# Stort_kredslob.net
KiCad netlist of a schematic drawn in EAGLE
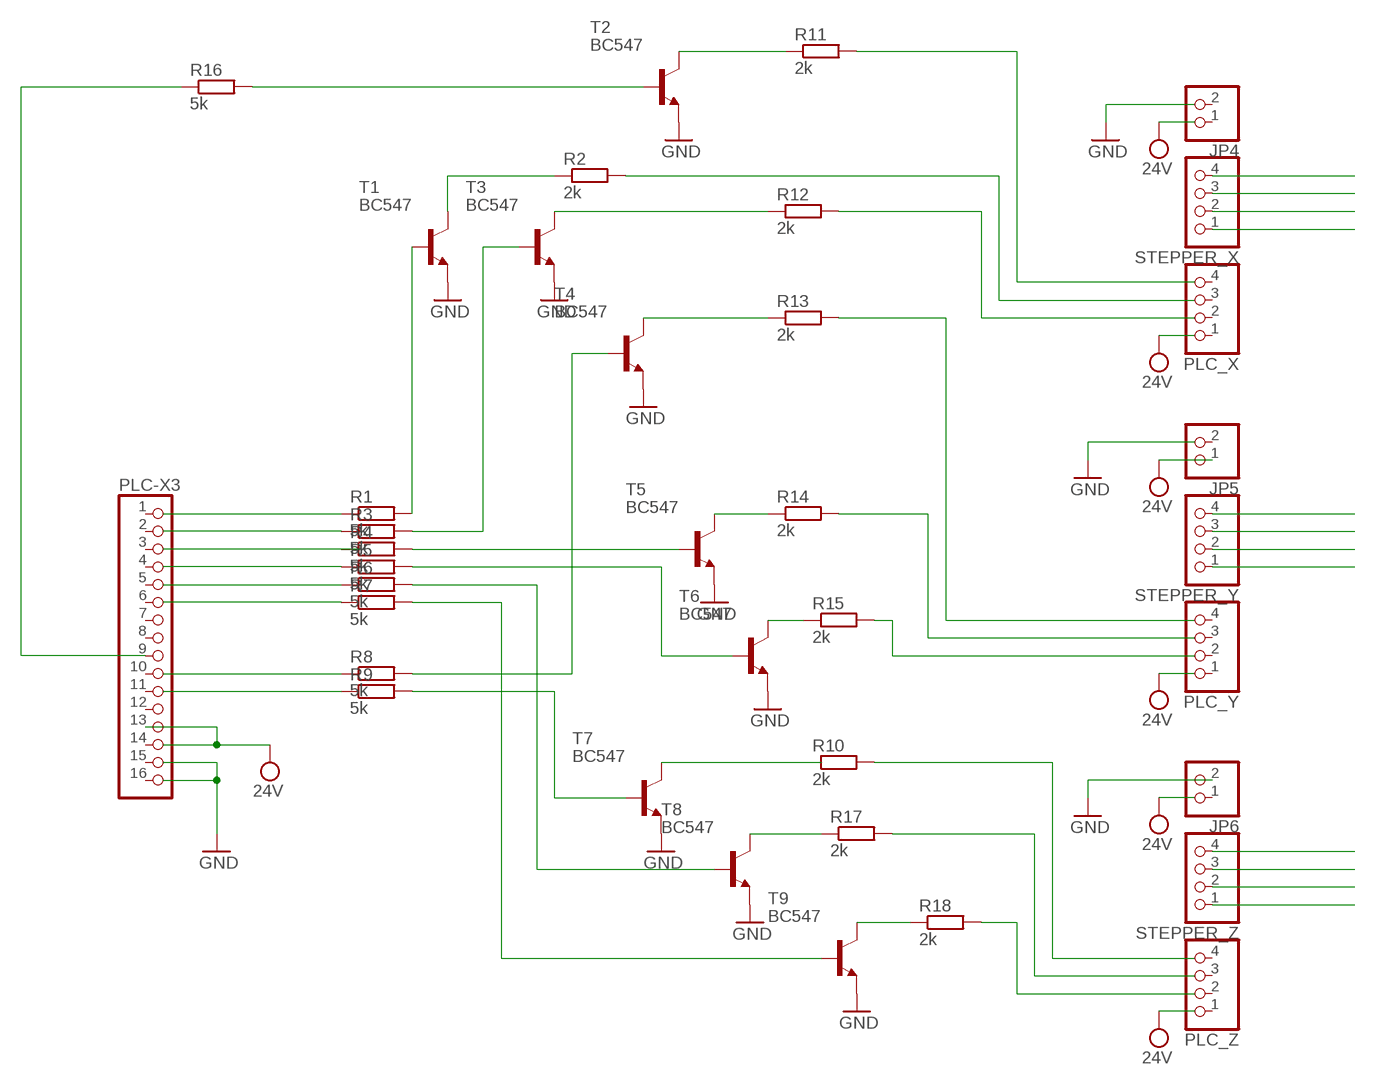
[diagram p0: schematic, sheet 1]

(export (version "E")
  (design (tool "Eeschema 10.0.6"))
  (components
    (comp (ref "JP4")
      (value "PINHD-1X2")
      (footprint "eagle-import:1X02")
      (libsource (lib "eagle-import") (part "PINHD-1X2"))
    )
    (comp (ref "JP5")
      (value "PINHD-1X2")
      (footprint "eagle-import:1X02")
      (libsource (lib "eagle-import") (part "PINHD-1X2"))
    )
    (comp (ref "JP6")
      (value "PINHD-1X2")
      (footprint "eagle-import:1X02")
      (libsource (lib "eagle-import") (part "PINHD-1X2"))
    )
    (comp (ref "PLC-X3")
      (value "PINHD-1X16")
      (footprint "eagle-import:1X16")
      (libsource (lib "eagle-import") (part "PINHD-1X16"))
    )
    (comp (ref "PLC_X")
      (value "PINHD-1X4")
      (footprint "eagle-import:1X04")
      (libsource (lib "eagle-import") (part "PINHD-1X4"))
    )
    (comp (ref "PLC_Y")
      (value "PINHD-1X4")
      (footprint "eagle-import:1X04")
      (libsource (lib "eagle-import") (part "PINHD-1X4"))
    )
    (comp (ref "PLC_Z")
      (value "PINHD-1X4")
      (footprint "eagle-import:1X04")
      (libsource (lib "eagle-import") (part "PINHD-1X4"))
    )
    (comp (ref "R1")
      (value "5k")
      (footprint "eagle-import:0207_10")
      (libsource (lib "eagle-import") (part "R-EU_0207/10"))
    )
    (comp (ref "R2")
      (value "2k")
      (footprint "eagle-import:0207_10")
      (libsource (lib "eagle-import") (part "R-EU_0207/10"))
    )
    (comp (ref "R3")
      (value "5k")
      (footprint "eagle-import:0207_10")
      (libsource (lib "eagle-import") (part "R-EU_0207/10"))
    )
    (comp (ref "R4")
      (value "5k")
      (footprint "eagle-import:0207_10")
      (libsource (lib "eagle-import") (part "R-EU_0207/10"))
    )
    (comp (ref "R5")
      (value "5k")
      (footprint "eagle-import:0207_10")
      (libsource (lib "eagle-import") (part "R-EU_0207/10"))
    )
    (comp (ref "R6")
      (value "5k")
      (footprint "eagle-import:0207_10")
      (libsource (lib "eagle-import") (part "R-EU_0207/10"))
    )
    (comp (ref "R7")
      (value "5k")
      (footprint "eagle-import:0207_10")
      (libsource (lib "eagle-import") (part "R-EU_0207/10"))
    )
    (comp (ref "R8")
      (value "5k")
      (footprint "eagle-import:0207_10")
      (libsource (lib "eagle-import") (part "R-EU_0207/10"))
    )
    (comp (ref "R9")
      (value "5k")
      (footprint "eagle-import:0207_10")
      (libsource (lib "eagle-import") (part "R-EU_0207/10"))
    )
    (comp (ref "R10")
      (value "2k")
      (footprint "eagle-import:0207_10")
      (libsource (lib "eagle-import") (part "R-EU_0207/10"))
    )
    (comp (ref "R11")
      (value "2k")
      (footprint "eagle-import:0207_10")
      (libsource (lib "eagle-import") (part "R-EU_0207/10"))
    )
    (comp (ref "R12")
      (value "2k")
      (footprint "eagle-import:0207_10")
      (libsource (lib "eagle-import") (part "R-EU_0207/10"))
    )
    (comp (ref "R13")
      (value "2k")
      (footprint "eagle-import:0207_10")
      (libsource (lib "eagle-import") (part "R-EU_0207/10"))
    )
    (comp (ref "R14")
      (value "2k")
      (footprint "eagle-import:0207_10")
      (libsource (lib "eagle-import") (part "R-EU_0207/10"))
    )
    (comp (ref "R15")
      (value "2k")
      (footprint "eagle-import:0207_10")
      (libsource (lib "eagle-import") (part "R-EU_0207/10"))
    )
    (comp (ref "R16")
      (value "5k")
      (footprint "eagle-import:0207_10")
      (libsource (lib "eagle-import") (part "R-EU_0207/10"))
    )
    (comp (ref "R17")
      (value "2k")
      (footprint "eagle-import:0207_10")
      (libsource (lib "eagle-import") (part "R-EU_0207/10"))
    )
    (comp (ref "R18")
      (value "2k")
      (footprint "eagle-import:0207_10")
      (libsource (lib "eagle-import") (part "R-EU_0207/10"))
    )
    (comp (ref "STEPPER_X")
      (value "PINHD-1X4")
      (footprint "eagle-import:1X04")
      (libsource (lib "eagle-import") (part "PINHD-1X4"))
    )
    (comp (ref "STEPPER_Y")
      (value "PINHD-1X4")
      (footprint "eagle-import:1X04")
      (libsource (lib "eagle-import") (part "PINHD-1X4"))
    )
    (comp (ref "STEPPER_Z")
      (value "PINHD-1X4")
      (footprint "eagle-import:1X04")
      (libsource (lib "eagle-import") (part "PINHD-1X4"))
    )
    (comp (ref "T1")
      (value "BC547")
      (footprint "eagle-import:TO92-E1")
      (libsource (lib "eagle-import") (part "-NPN-TO92-E1"))
    )
    (comp (ref "T2")
      (value "BC547")
      (footprint "eagle-import:TO92-E1")
      (libsource (lib "eagle-import") (part "-NPN-TO92-E1"))
    )
    (comp (ref "T3")
      (value "BC547")
      (footprint "eagle-import:TO92-E1")
      (libsource (lib "eagle-import") (part "-NPN-TO92-E1"))
    )
    (comp (ref "T4")
      (value "BC547")
      (footprint "eagle-import:TO92-E1")
      (libsource (lib "eagle-import") (part "-NPN-TO92-E1"))
    )
    (comp (ref "T5")
      (value "BC547")
      (footprint "eagle-import:TO92-E1")
      (libsource (lib "eagle-import") (part "-NPN-TO92-E1"))
    )
    (comp (ref "T6")
      (value "BC547")
      (footprint "eagle-import:TO92-E1")
      (libsource (lib "eagle-import") (part "-NPN-TO92-E1"))
    )
    (comp (ref "T7")
      (value "BC547")
      (footprint "eagle-import:TO92-E1")
      (libsource (lib "eagle-import") (part "-NPN-TO92-E1"))
    )
    (comp (ref "T8")
      (value "BC547")
      (footprint "eagle-import:TO92-E1")
      (libsource (lib "eagle-import") (part "-NPN-TO92-E1"))
    )
    (comp (ref "T9")
      (value "BC547")
      (footprint "eagle-import:TO92-E1")
      (libsource (lib "eagle-import") (part "-NPN-TO92-E1"))
    )
  )
  (nets
    (net (code "1") (name "24V") (class "Default")
      (node (ref "JP5") (pin "1") (pinfunction "1_1") (pintype "passive"))
      (node (ref "PLC-X3") (pin "13") (pinfunction "13_13") (pintype "passive"))
    )
    (net (code "2") (name "GND") (class "Default")
      (node (ref "JP6") (pin "2") (pinfunction "2_2") (pintype "passive"))
      (node (ref "T1") (pin "3") (pinfunction "E_3") (pintype "passive"))
      (node (ref "T2") (pin "3") (pinfunction "E_3") (pintype "passive"))
      (node (ref "T3") (pin "3") (pinfunction "E_3") (pintype "passive"))
      (node (ref "T4") (pin "3") (pinfunction "E_3") (pintype "passive"))
      (node (ref "T5") (pin "3") (pinfunction "E_3") (pintype "passive"))
      (node (ref "T6") (pin "3") (pinfunction "E_3") (pintype "passive"))
      (node (ref "T7") (pin "3") (pinfunction "E_3") (pintype "passive"))
      (node (ref "T8") (pin "3") (pinfunction "E_3") (pintype "passive"))
      (node (ref "T9") (pin "3") (pinfunction "E_3") (pintype "passive"))
    )
    (net (code "3") (name "Net-(PLC-X3-Pad9)") (class "Default")
      (node (ref "PLC-X3") (pin "9") (pinfunction "9_9") (pintype "passive"))
      (node (ref "R16") (pin "1") (pinfunction "1_1") (pintype "passive"))
    )
    (net (code "4") (name "Net-(T1-B)") (class "Default")
      (node (ref "R1") (pin "2") (pinfunction "2_2") (pintype "passive"))
      (node (ref "T1") (pin "2") (pinfunction "B_2") (pintype "passive"))
    )
    (net (code "5") (name "Net-(T1-C)") (class "Default")
      (node (ref "R2") (pin "1") (pinfunction "1_1") (pintype "passive"))
      (node (ref "T1") (pin "1") (pinfunction "C_1") (pintype "passive"))
    )
    (net (code "6") (name "Net-(T2-B)") (class "Default")
      (node (ref "R16") (pin "2") (pinfunction "2_2") (pintype "passive"))
      (node (ref "T2") (pin "2") (pinfunction "B_2") (pintype "passive"))
    )
    (net (code "7") (name "Net-(T2-C)") (class "Default")
      (node (ref "R11") (pin "1") (pinfunction "1_1") (pintype "passive"))
      (node (ref "T2") (pin "1") (pinfunction "C_1") (pintype "passive"))
    )
    (net (code "8") (name "Net-(T3-B)") (class "Default")
      (node (ref "R3") (pin "2") (pinfunction "2_2") (pintype "passive"))
      (node (ref "T3") (pin "2") (pinfunction "B_2") (pintype "passive"))
    )
    (net (code "9") (name "Net-(T3-C)") (class "Default")
      (node (ref "R12") (pin "1") (pinfunction "1_1") (pintype "passive"))
      (node (ref "T3") (pin "1") (pinfunction "C_1") (pintype "passive"))
    )
    (net (code "10") (name "Net-(T4-B)") (class "Default")
      (node (ref "R8") (pin "2") (pinfunction "2_2") (pintype "passive"))
      (node (ref "T4") (pin "2") (pinfunction "B_2") (pintype "passive"))
    )
    (net (code "11") (name "Net-(T4-C)") (class "Default")
      (node (ref "R13") (pin "1") (pinfunction "1_1") (pintype "passive"))
      (node (ref "T4") (pin "1") (pinfunction "C_1") (pintype "passive"))
    )
    (net (code "12") (name "Net-(T5-B)") (class "Default")
      (node (ref "R4") (pin "2") (pinfunction "2_2") (pintype "passive"))
      (node (ref "T5") (pin "2") (pinfunction "B_2") (pintype "passive"))
    )
    (net (code "13") (name "Net-(T5-C)") (class "Default")
      (node (ref "R14") (pin "1") (pinfunction "1_1") (pintype "passive"))
      (node (ref "T5") (pin "1") (pinfunction "C_1") (pintype "passive"))
    )
    (net (code "14") (name "Net-(T6-B)") (class "Default")
      (node (ref "R5") (pin "2") (pinfunction "2_2") (pintype "passive"))
      (node (ref "T6") (pin "2") (pinfunction "B_2") (pintype "passive"))
    )
    (net (code "15") (name "Net-(T6-C)") (class "Default")
      (node (ref "R15") (pin "1") (pinfunction "1_1") (pintype "passive"))
      (node (ref "T6") (pin "1") (pinfunction "C_1") (pintype "passive"))
    )
    (net (code "16") (name "Net-(T7-B)") (class "Default")
      (node (ref "R9") (pin "2") (pinfunction "2_2") (pintype "passive"))
      (node (ref "T7") (pin "2") (pinfunction "B_2") (pintype "passive"))
    )
    (net (code "17") (name "Net-(T7-C)") (class "Default")
      (node (ref "R10") (pin "1") (pinfunction "1_1") (pintype "passive"))
      (node (ref "T7") (pin "1") (pinfunction "C_1") (pintype "passive"))
    )
    (net (code "18") (name "Net-(T8-B)") (class "Default")
      (node (ref "R6") (pin "2") (pinfunction "2_2") (pintype "passive"))
      (node (ref "T8") (pin "2") (pinfunction "B_2") (pintype "passive"))
    )
    (net (code "19") (name "Net-(T8-C)") (class "Default")
      (node (ref "R17") (pin "1") (pinfunction "1_1") (pintype "passive"))
      (node (ref "T8") (pin "1") (pinfunction "C_1") (pintype "passive"))
    )
    (net (code "20") (name "Net-(T9-B)") (class "Default")
      (node (ref "R7") (pin "2") (pinfunction "2_2") (pintype "passive"))
      (node (ref "T9") (pin "2") (pinfunction "B_2") (pintype "passive"))
    )
    (net (code "21") (name "Net-(T9-C)") (class "Default")
      (node (ref "R18") (pin "1") (pinfunction "1_1") (pintype "passive"))
      (node (ref "T9") (pin "1") (pinfunction "C_1") (pintype "passive"))
    )
    (net (code "22") (name "unconnected-(JP4-Pad1)") (class "Default")
      (node (ref "JP4") (pin "1") (pinfunction "1_1") (pintype "passive"))
    )
    (net (code "23") (name "unconnected-(JP4-Pad2)") (class "Default")
      (node (ref "JP4") (pin "2") (pinfunction "2_2") (pintype "passive"))
    )
    (net (code "24") (name "unconnected-(JP5-Pad2)") (class "Default")
      (node (ref "JP5") (pin "2") (pinfunction "2_2") (pintype "passive"))
    )
    (net (code "25") (name "unconnected-(JP6-Pad1)") (class "Default")
      (node (ref "JP6") (pin "1") (pinfunction "1_1") (pintype "passive"))
    )
    (net (code "26") (name "unconnected-(PLC-X3-Pad1)") (class "Default")
      (node (ref "PLC-X3") (pin "1") (pinfunction "1_1") (pintype "passive"))
    )
    (net (code "27") (name "unconnected-(PLC-X3-Pad2)") (class "Default")
      (node (ref "PLC-X3") (pin "2") (pinfunction "2_2") (pintype "passive"))
    )
    (net (code "28") (name "unconnected-(PLC-X3-Pad3)") (class "Default")
      (node (ref "PLC-X3") (pin "3") (pinfunction "3_3") (pintype "passive"))
    )
    (net (code "29") (name "unconnected-(PLC-X3-Pad4)") (class "Default")
      (node (ref "PLC-X3") (pin "4") (pinfunction "4_4") (pintype "passive"))
    )
    (net (code "30") (name "unconnected-(PLC-X3-Pad5)") (class "Default")
      (node (ref "PLC-X3") (pin "5") (pinfunction "5_5") (pintype "passive"))
    )
    (net (code "31") (name "unconnected-(PLC-X3-Pad6)") (class "Default")
      (node (ref "PLC-X3") (pin "6") (pinfunction "6_6") (pintype "passive"))
    )
    (net (code "32") (name "unconnected-(PLC-X3-Pad7)") (class "Default")
      (node (ref "PLC-X3") (pin "7") (pinfunction "7_7") (pintype "passive"))
    )
    (net (code "33") (name "unconnected-(PLC-X3-Pad8)") (class "Default")
      (node (ref "PLC-X3") (pin "8") (pinfunction "8_8") (pintype "passive"))
    )
    (net (code "34") (name "unconnected-(PLC-X3-Pad10)") (class "Default")
      (node (ref "PLC-X3") (pin "10") (pinfunction "10_10") (pintype "passive"))
    )
    (net (code "35") (name "unconnected-(PLC-X3-Pad11)") (class "Default")
      (node (ref "PLC-X3") (pin "11") (pinfunction "11_11") (pintype "passive"))
    )
    (net (code "36") (name "unconnected-(PLC-X3-Pad12)") (class "Default")
      (node (ref "PLC-X3") (pin "12") (pinfunction "12_12") (pintype "passive"))
    )
    (net (code "37") (name "unconnected-(PLC-X3-Pad14)") (class "Default")
      (node (ref "PLC-X3") (pin "14") (pinfunction "14_14") (pintype "passive"))
    )
    (net (code "38") (name "unconnected-(PLC-X3-Pad15)") (class "Default")
      (node (ref "PLC-X3") (pin "15") (pinfunction "15_15") (pintype "passive"))
    )
    (net (code "39") (name "unconnected-(PLC-X3-Pad16)") (class "Default")
      (node (ref "PLC-X3") (pin "16") (pinfunction "16_16") (pintype "passive"))
    )
    (net (code "40") (name "unconnected-(PLC_X-Pad1)") (class "Default")
      (node (ref "PLC_X") (pin "1") (pinfunction "1_1") (pintype "passive"))
    )
    (net (code "41") (name "unconnected-(PLC_X-Pad2)") (class "Default")
      (node (ref "PLC_X") (pin "2") (pinfunction "2_2") (pintype "passive"))
    )
    (net (code "42") (name "unconnected-(PLC_X-Pad3)") (class "Default")
      (node (ref "PLC_X") (pin "3") (pinfunction "3_3") (pintype "passive"))
    )
    (net (code "43") (name "unconnected-(PLC_X-Pad4)") (class "Default")
      (node (ref "PLC_X") (pin "4") (pinfunction "4_4") (pintype "passive"))
    )
    (net (code "44") (name "unconnected-(PLC_Y-Pad1)") (class "Default")
      (node (ref "PLC_Y") (pin "1") (pinfunction "1_1") (pintype "passive"))
    )
    (net (code "45") (name "unconnected-(PLC_Y-Pad2)") (class "Default")
      (node (ref "PLC_Y") (pin "2") (pinfunction "2_2") (pintype "passive"))
    )
    (net (code "46") (name "unconnected-(PLC_Y-Pad3)") (class "Default")
      (node (ref "PLC_Y") (pin "3") (pinfunction "3_3") (pintype "passive"))
    )
    (net (code "47") (name "unconnected-(PLC_Y-Pad4)") (class "Default")
      (node (ref "PLC_Y") (pin "4") (pinfunction "4_4") (pintype "passive"))
    )
    (net (code "48") (name "unconnected-(PLC_Z-Pad1)") (class "Default")
      (node (ref "PLC_Z") (pin "1") (pinfunction "1_1") (pintype "passive"))
    )
    (net (code "49") (name "unconnected-(PLC_Z-Pad2)") (class "Default")
      (node (ref "PLC_Z") (pin "2") (pinfunction "2_2") (pintype "passive"))
    )
    (net (code "50") (name "unconnected-(PLC_Z-Pad3)") (class "Default")
      (node (ref "PLC_Z") (pin "3") (pinfunction "3_3") (pintype "passive"))
    )
    (net (code "51") (name "unconnected-(PLC_Z-Pad4)") (class "Default")
      (node (ref "PLC_Z") (pin "4") (pinfunction "4_4") (pintype "passive"))
    )
    (net (code "52") (name "unconnected-(R1-Pad1)") (class "Default")
      (node (ref "R1") (pin "1") (pinfunction "1_1") (pintype "passive"))
    )
    (net (code "53") (name "unconnected-(R2-Pad2)") (class "Default")
      (node (ref "R2") (pin "2") (pinfunction "2_2") (pintype "passive"))
    )
    (net (code "54") (name "unconnected-(R3-Pad1)") (class "Default")
      (node (ref "R3") (pin "1") (pinfunction "1_1") (pintype "passive"))
    )
    (net (code "55") (name "unconnected-(R4-Pad1)") (class "Default")
      (node (ref "R4") (pin "1") (pinfunction "1_1") (pintype "passive"))
    )
    (net (code "56") (name "unconnected-(R5-Pad1)") (class "Default")
      (node (ref "R5") (pin "1") (pinfunction "1_1") (pintype "passive"))
    )
    (net (code "57") (name "unconnected-(R6-Pad1)") (class "Default")
      (node (ref "R6") (pin "1") (pinfunction "1_1") (pintype "passive"))
    )
    (net (code "58") (name "unconnected-(R7-Pad1)") (class "Default")
      (node (ref "R7") (pin "1") (pinfunction "1_1") (pintype "passive"))
    )
    (net (code "59") (name "unconnected-(R8-Pad1)") (class "Default")
      (node (ref "R8") (pin "1") (pinfunction "1_1") (pintype "passive"))
    )
    (net (code "60") (name "unconnected-(R9-Pad1)") (class "Default")
      (node (ref "R9") (pin "1") (pinfunction "1_1") (pintype "passive"))
    )
    (net (code "61") (name "unconnected-(R10-Pad2)") (class "Default")
      (node (ref "R10") (pin "2") (pinfunction "2_2") (pintype "passive"))
    )
    (net (code "62") (name "unconnected-(R11-Pad2)") (class "Default")
      (node (ref "R11") (pin "2") (pinfunction "2_2") (pintype "passive"))
    )
    (net (code "63") (name "unconnected-(R12-Pad2)") (class "Default")
      (node (ref "R12") (pin "2") (pinfunction "2_2") (pintype "passive"))
    )
    (net (code "64") (name "unconnected-(R13-Pad2)") (class "Default")
      (node (ref "R13") (pin "2") (pinfunction "2_2") (pintype "passive"))
    )
    (net (code "65") (name "unconnected-(R14-Pad2)") (class "Default")
      (node (ref "R14") (pin "2") (pinfunction "2_2") (pintype "passive"))
    )
    (net (code "66") (name "unconnected-(R15-Pad2)") (class "Default")
      (node (ref "R15") (pin "2") (pinfunction "2_2") (pintype "passive"))
    )
    (net (code "67") (name "unconnected-(R17-Pad2)") (class "Default")
      (node (ref "R17") (pin "2") (pinfunction "2_2") (pintype "passive"))
    )
    (net (code "68") (name "unconnected-(R18-Pad2)") (class "Default")
      (node (ref "R18") (pin "2") (pinfunction "2_2") (pintype "passive"))
    )
    (net (code "69") (name "unconnected-(STEPPER_X-Pad1)") (class "Default")
      (node (ref "STEPPER_X") (pin "1") (pinfunction "1_1") (pintype "passive"))
    )
    (net (code "70") (name "unconnected-(STEPPER_X-Pad2)") (class "Default")
      (node (ref "STEPPER_X") (pin "2") (pinfunction "2_2") (pintype "passive"))
    )
    (net (code "71") (name "unconnected-(STEPPER_X-Pad3)") (class "Default")
      (node (ref "STEPPER_X") (pin "3") (pinfunction "3_3") (pintype "passive"))
    )
    (net (code "72") (name "unconnected-(STEPPER_X-Pad4)") (class "Default")
      (node (ref "STEPPER_X") (pin "4") (pinfunction "4_4") (pintype "passive"))
    )
    (net (code "73") (name "unconnected-(STEPPER_Y-Pad1)") (class "Default")
      (node (ref "STEPPER_Y") (pin "1") (pinfunction "1_1") (pintype "passive"))
    )
    (net (code "74") (name "unconnected-(STEPPER_Y-Pad2)") (class "Default")
      (node (ref "STEPPER_Y") (pin "2") (pinfunction "2_2") (pintype "passive"))
    )
    (net (code "75") (name "unconnected-(STEPPER_Y-Pad3)") (class "Default")
      (node (ref "STEPPER_Y") (pin "3") (pinfunction "3_3") (pintype "passive"))
    )
    (net (code "76") (name "unconnected-(STEPPER_Y-Pad4)") (class "Default")
      (node (ref "STEPPER_Y") (pin "4") (pinfunction "4_4") (pintype "passive"))
    )
    (net (code "77") (name "unconnected-(STEPPER_Z-Pad1)") (class "Default")
      (node (ref "STEPPER_Z") (pin "1") (pinfunction "1_1") (pintype "passive"))
    )
    (net (code "78") (name "unconnected-(STEPPER_Z-Pad2)") (class "Default")
      (node (ref "STEPPER_Z") (pin "2") (pinfunction "2_2") (pintype "passive"))
    )
    (net (code "79") (name "unconnected-(STEPPER_Z-Pad3)") (class "Default")
      (node (ref "STEPPER_Z") (pin "3") (pinfunction "3_3") (pintype "passive"))
    )
    (net (code "80") (name "unconnected-(STEPPER_Z-Pad4)") (class "Default")
      (node (ref "STEPPER_Z") (pin "4") (pinfunction "4_4") (pintype "passive"))
    )
  )
)
